# 09_NAND.net
KiCad netlist of a schematic drawn in Altium Designer
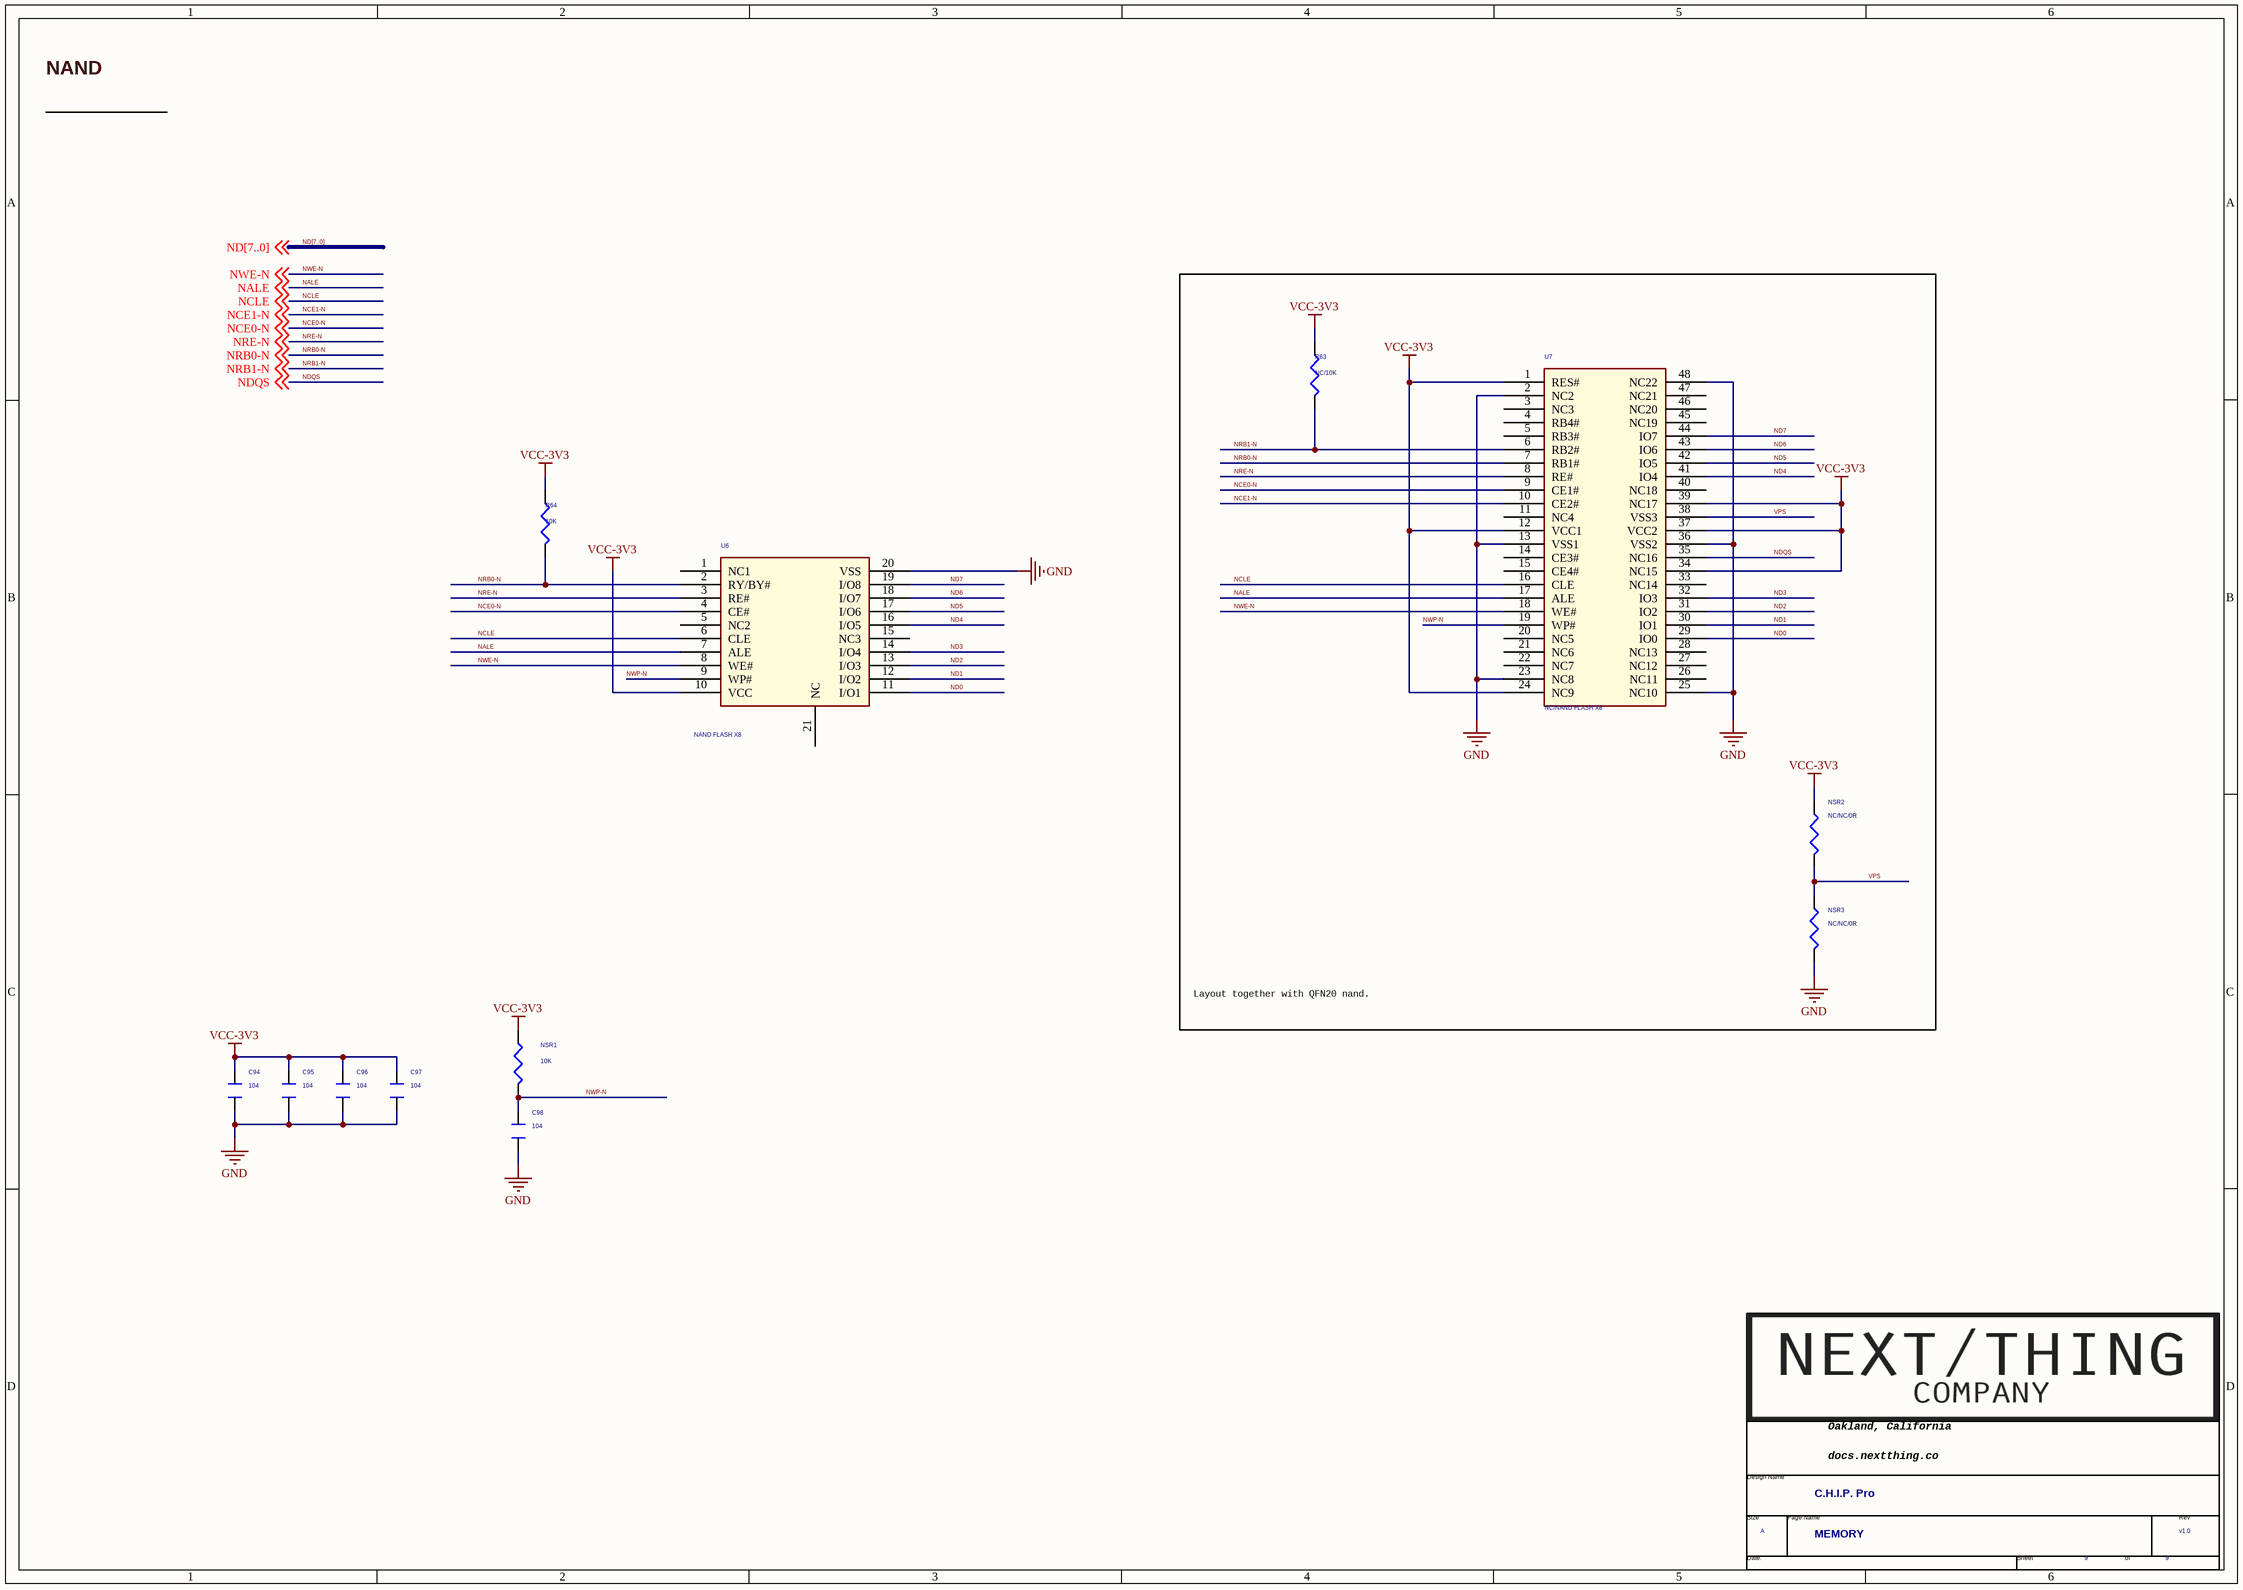
[diagram p0: 09 NAND.SchDoc]

(export (version "E")
  (design (tool "Eeschema 10.0.6"))
  (components
    (comp (ref "C94") (value "104") (footprint "C0201") (libsource (lib "*") (part "CAPACITOR_0_Dup4")))
    (comp (ref "C95") (value "104") (footprint "C0201") (libsource (lib "*") (part "CAPACITOR_0_Dup4")))
    (comp (ref "C96") (value "104") (footprint "C0201") (libsource (lib "*") (part "CAPACITOR_0_Dup4")))
    (comp (ref "C97") (value "104") (footprint "C0201") (libsource (lib "*") (part "CAPACITOR_0_Dup4")))
    (comp (ref "C98") (value "104") (footprint "C0201") (libsource (lib "*") (part "CAPACITOR_0_Dup4")))
    (comp (ref "NSR1") (value "10K") (footprint "R0201") (libsource (lib "*") (part "R_Dup2")))
    (comp (ref "NSR2") (value "NC/NC/0R") (footprint "R0201") (libsource (lib "*") (part "R_Dup2")))
    (comp (ref "NSR3") (value "NC/NC/0R") (footprint "R0201") (libsource (lib "*") (part "R_Dup2")))
    (comp (ref "R63") (value "NC/10K") (footprint "R0201") (libsource (lib "*") (part "R_Dup2")))
    (comp (ref "R64") (value "10K") (footprint "R0201") (libsource (lib "*") (part "R_Dup2")))
    (comp (ref "U6")
      (value "NAND FLASH X8")
      (footprint "TSOP-48")
      (libsource (lib "*") (part "NAND_QFN20_1"))
    )
    (comp (ref "U7")
      (value "NC/NAND FLASH X8")
      (footprint "TSOP-48")
      (libsource (lib "*") (part "NAND_FLASH_X8"))
    )
  )
  (nets
    (net (code "1") (name "/NWP-N") (class "Default")
      (node (ref "C98") (pin "2") (pinfunction "2_2") (pintype "passive"))
      (node (ref "NSR1") (pin "2") (pinfunction "2_2") (pintype "passive"))
      (node (ref "U6") (pin "9") (pinfunction "WP#_9") (pintype "passive"))
      (node (ref "U7") (pin "19") (pinfunction "WP#_19") (pintype "passive"))
    )
    (net (code "2") (name "/VPS") (class "Default")
      (node (ref "NSR2") (pin "2") (pinfunction "2_2") (pintype "passive"))
      (node (ref "NSR3") (pin "1") (pinfunction "1_1") (pintype "passive"))
      (node (ref "U7") (pin "38") (pinfunction "VSS3_38") (pintype "passive"))
    )
    (net (code "3") (name "GND") (class "Default")
      (node (ref "C94") (pin "1") (pinfunction "1_1") (pintype "passive"))
      (node (ref "C95") (pin "1") (pinfunction "1_1") (pintype "passive"))
      (node (ref "C96") (pin "1") (pinfunction "1_1") (pintype "passive"))
      (node (ref "C97") (pin "1") (pinfunction "1_1") (pintype "passive"))
      (node (ref "C98") (pin "1") (pinfunction "1_1") (pintype "passive"))
      (node (ref "NSR3") (pin "2") (pinfunction "2_2") (pintype "passive"))
      (node (ref "U6") (pin "20") (pinfunction "VSS_20") (pintype "passive"))
      (node (ref "U7") (pin "13") (pinfunction "VSS1_13") (pintype "passive"))
      (node (ref "U7") (pin "2") (pinfunction "NC2_2") (pintype "passive"))
      (node (ref "U7") (pin "23") (pinfunction "NC8_23") (pintype "passive"))
      (node (ref "U7") (pin "25") (pinfunction "NC10_25") (pintype "passive"))
      (node (ref "U7") (pin "36") (pinfunction "VSS2_36") (pintype "passive"))
      (node (ref "U7") (pin "48") (pinfunction "NC22_48") (pintype "passive"))
    )
    (net (code "4") (name "NALE") (class "Default")
      (node (ref "U6") (pin "7") (pinfunction "ALE_7") (pintype "passive"))
      (node (ref "U7") (pin "17") (pinfunction "ALE_17") (pintype "passive"))
    )
    (net (code "5") (name "NCE0-N") (class "Default")
      (node (ref "U6") (pin "4") (pinfunction "CE#_4") (pintype "passive"))
      (node (ref "U7") (pin "9") (pinfunction "CE1#_9") (pintype "passive"))
    )
    (net (code "6") (name "NCE1-N") (class "Default")
      (node (ref "U7") (pin "10") (pinfunction "CE2#_10") (pintype "passive"))
    )
    (net (code "7") (name "NCLE") (class "Default")
      (node (ref "U6") (pin "6") (pinfunction "CLE_6") (pintype "passive"))
      (node (ref "U7") (pin "16") (pinfunction "CLE_16") (pintype "passive"))
    )
    (net (code "8") (name "ND0") (class "Default")
      (node (ref "U6") (pin "11") (pinfunction "I/O1_11") (pintype "passive"))
      (node (ref "U7") (pin "29") (pinfunction "IO0_29") (pintype "passive"))
    )
    (net (code "9") (name "ND1") (class "Default")
      (node (ref "U6") (pin "12") (pinfunction "I/O2_12") (pintype "passive"))
      (node (ref "U7") (pin "30") (pinfunction "IO1_30") (pintype "passive"))
    )
    (net (code "10") (name "ND2") (class "Default")
      (node (ref "U6") (pin "13") (pinfunction "I/O3_13") (pintype "passive"))
      (node (ref "U7") (pin "31") (pinfunction "IO2_31") (pintype "passive"))
    )
    (net (code "11") (name "ND3") (class "Default")
      (node (ref "U6") (pin "14") (pinfunction "I/O4_14") (pintype "passive"))
      (node (ref "U7") (pin "32") (pinfunction "IO3_32") (pintype "passive"))
    )
    (net (code "12") (name "ND4") (class "Default")
      (node (ref "U6") (pin "16") (pinfunction "I/O5_16") (pintype "passive"))
      (node (ref "U7") (pin "41") (pinfunction "IO4_41") (pintype "passive"))
    )
    (net (code "13") (name "ND5") (class "Default")
      (node (ref "U6") (pin "17") (pinfunction "I/O6_17") (pintype "passive"))
      (node (ref "U7") (pin "42") (pinfunction "IO5_42") (pintype "passive"))
    )
    (net (code "14") (name "ND6") (class "Default")
      (node (ref "U6") (pin "18") (pinfunction "I/O7_18") (pintype "passive"))
      (node (ref "U7") (pin "43") (pinfunction "IO6_43") (pintype "passive"))
    )
    (net (code "15") (name "ND7") (class "Default")
      (node (ref "U6") (pin "19") (pinfunction "I/O8_19") (pintype "passive"))
      (node (ref "U7") (pin "44") (pinfunction "IO7_44") (pintype "passive"))
    )
    (net (code "16") (name "NDQS") (class "Default")
      (node (ref "U7") (pin "35") (pinfunction "NC16_35") (pintype "passive"))
    )
    (net (code "18") (name "NRB0-N") (class "Default")
      (node (ref "R64") (pin "2") (pinfunction "2_2") (pintype "passive"))
      (node (ref "U6") (pin "2") (pinfunction "RY/BY#_2") (pintype "passive"))
      (node (ref "U7") (pin "7") (pinfunction "RB1#_7") (pintype "passive"))
    )
    (net (code "19") (name "NRB1-N") (class "Default")
      (node (ref "R63") (pin "2") (pinfunction "2_2") (pintype "passive"))
      (node (ref "U7") (pin "6") (pinfunction "RB2#_6") (pintype "passive"))
    )
    (net (code "20") (name "NRE-N") (class "Default")
      (node (ref "U6") (pin "3") (pinfunction "RE#_3") (pintype "passive"))
      (node (ref "U7") (pin "8") (pinfunction "RE#_8") (pintype "passive"))
    )
    (net (code "21") (name "NWE-N") (class "Default")
      (node (ref "U6") (pin "8") (pinfunction "WE#_8") (pintype "passive"))
      (node (ref "U7") (pin "18") (pinfunction "WE#_18") (pintype "passive"))
    )
    (net (code "22") (name "VCC-3V3") (class "Default")
      (node (ref "C94") (pin "2") (pinfunction "2_2") (pintype "passive"))
      (node (ref "C95") (pin "2") (pinfunction "2_2") (pintype "passive"))
      (node (ref "C96") (pin "2") (pinfunction "2_2") (pintype "passive"))
      (node (ref "C97") (pin "2") (pinfunction "2_2") (pintype "passive"))
      (node (ref "NSR1") (pin "1") (pinfunction "1_1") (pintype "passive"))
      (node (ref "NSR2") (pin "1") (pinfunction "1_1") (pintype "passive"))
      (node (ref "R63") (pin "1") (pinfunction "1_1") (pintype "passive"))
      (node (ref "R64") (pin "1") (pinfunction "1_1") (pintype "passive"))
      (node (ref "U6") (pin "10") (pinfunction "VCC_10") (pintype "passive"))
      (node (ref "U7") (pin "1") (pinfunction "RES#_1") (pintype "passive"))
      (node (ref "U7") (pin "12") (pinfunction "VCC1_12") (pintype "passive"))
      (node (ref "U7") (pin "24") (pinfunction "NC9_24") (pintype "passive"))
      (node (ref "U7") (pin "34") (pinfunction "NC15_34") (pintype "passive"))
      (node (ref "U7") (pin "37") (pinfunction "VCC2_37") (pintype "passive"))
      (node (ref "U7") (pin "39") (pinfunction "NC17_39") (pintype "passive"))
    )
    (net (code "23") (name "unconnected-(U6-NC-Pad21)") (class "Default")
      (node (ref "U6") (pin "21") (pinfunction "NC_21") (pintype "passive"))
    )
    (net (code "24") (name "unconnected-(U6-NC1-Pad1)") (class "Default")
      (node (ref "U6") (pin "1") (pinfunction "NC1_1") (pintype "passive"))
    )
    (net (code "25") (name "unconnected-(U6-NC2-Pad5)") (class "Default")
      (node (ref "U6") (pin "5") (pinfunction "NC2_5") (pintype "passive"))
    )
    (net (code "26") (name "unconnected-(U6-NC3-Pad15)") (class "Default")
      (node (ref "U6") (pin "15") (pinfunction "NC3_15") (pintype "passive"))
    )
    (net (code "27") (name "unconnected-(U7-CE3#-Pad14)") (class "Default")
      (node (ref "U7") (pin "14") (pinfunction "CE3#_14") (pintype "passive"))
    )
    (net (code "28") (name "unconnected-(U7-CE4#-Pad15)") (class "Default")
      (node (ref "U7") (pin "15") (pinfunction "CE4#_15") (pintype "passive"))
    )
    (net (code "29") (name "unconnected-(U7-NC3-Pad3)") (class "Default")
      (node (ref "U7") (pin "3") (pinfunction "NC3_3") (pintype "passive"))
    )
    (net (code "30") (name "unconnected-(U7-NC4-Pad11)") (class "Default")
      (node (ref "U7") (pin "11") (pinfunction "NC4_11") (pintype "passive"))
    )
    (net (code "31") (name "unconnected-(U7-NC5-Pad20)") (class "Default")
      (node (ref "U7") (pin "20") (pinfunction "NC5_20") (pintype "passive"))
    )
    (net (code "32") (name "unconnected-(U7-NC6-Pad21)") (class "Default")
      (node (ref "U7") (pin "21") (pinfunction "NC6_21") (pintype "passive"))
    )
    (net (code "33") (name "unconnected-(U7-NC7-Pad22)") (class "Default")
      (node (ref "U7") (pin "22") (pinfunction "NC7_22") (pintype "passive"))
    )
    (net (code "34") (name "unconnected-(U7-NC11-Pad26)") (class "Default")
      (node (ref "U7") (pin "26") (pinfunction "NC11_26") (pintype "passive"))
    )
    (net (code "35") (name "unconnected-(U7-NC12-Pad27)") (class "Default")
      (node (ref "U7") (pin "27") (pinfunction "NC12_27") (pintype "passive"))
    )
    (net (code "36") (name "unconnected-(U7-NC13-Pad28)") (class "Default")
      (node (ref "U7") (pin "28") (pinfunction "NC13_28") (pintype "passive"))
    )
    (net (code "37") (name "unconnected-(U7-NC14-Pad33)") (class "Default")
      (node (ref "U7") (pin "33") (pinfunction "NC14_33") (pintype "passive"))
    )
    (net (code "38") (name "unconnected-(U7-NC18-Pad40)") (class "Default")
      (node (ref "U7") (pin "40") (pinfunction "NC18_40") (pintype "passive"))
    )
    (net (code "39") (name "unconnected-(U7-NC19-Pad45)") (class "Default")
      (node (ref "U7") (pin "45") (pinfunction "NC19_45") (pintype "passive"))
    )
    (net (code "40") (name "unconnected-(U7-NC20-Pad46)") (class "Default")
      (node (ref "U7") (pin "46") (pinfunction "NC20_46") (pintype "passive"))
    )
    (net (code "41") (name "unconnected-(U7-NC21-Pad47)") (class "Default")
      (node (ref "U7") (pin "47") (pinfunction "NC21_47") (pintype "passive"))
    )
    (net (code "42") (name "unconnected-(U7-RB3#-Pad5)") (class "Default")
      (node (ref "U7") (pin "5") (pinfunction "RB3#_5") (pintype "passive"))
    )
    (net (code "43") (name "unconnected-(U7-RB4#-Pad4)") (class "Default")
      (node (ref "U7") (pin "4") (pinfunction "RB4#_4") (pintype "passive"))
    )
  )
)
